# SolarPwrOptions.net
KiCad netlist of a schematic drawn in EAGLE
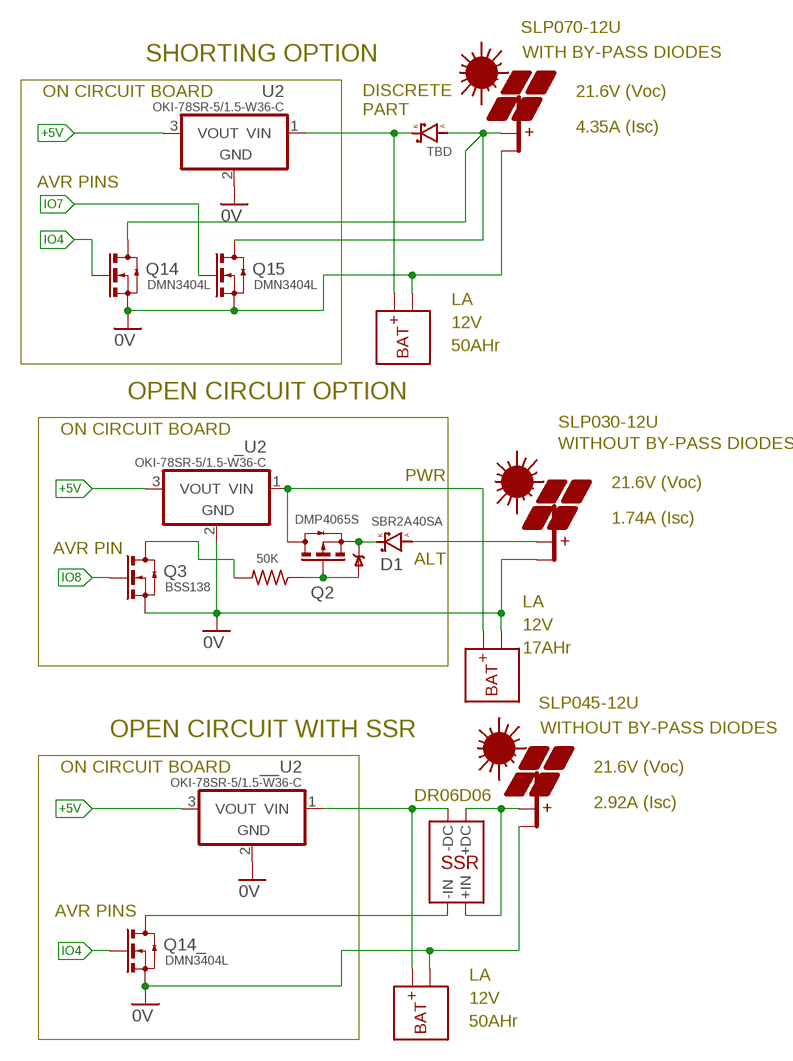
[diagram p0: schematic, sheet 1]

(export (version "E")
  (design (tool "Eeschema 10.0.6"))
  (components
    (comp (ref "D1")
      (value "SBR2A40SA")
      (footprint "eagle-import:SMB")
      (libsource (lib "eagle-import") (part "DSMB"))
    )
    (comp (ref "D3")
      (value "TVSSMC")
      (footprint "eagle-import:SMC")
      (libsource (lib "eagle-import") (part "TVSSMC"))
    )
    (comp (ref "PV1")
      (value "PV")
      (footprint "eagle-import:NA-30")
      (libsource (lib "eagle-import") (part "PV"))
    )
    (comp (ref "PV2")
      (value "PV")
      (footprint "eagle-import:NA-30")
      (libsource (lib "eagle-import") (part "PV"))
    )
    (comp (ref "PV3")
      (value "PV")
      (footprint "eagle-import:NA-30")
      (libsource (lib "eagle-import") (part "PV"))
    )
    (comp (ref "Q2")
      (value "DMP4065S")
      (footprint "eagle-import:DPAK")
      (libsource (lib "eagle-import") (part "Q-PCH_N-CH?DPAK"))
    )
    (comp (ref "Q3")
      (value "BSS138")
      (footprint "eagle-import:DPAK")
      (libsource (lib "eagle-import") (part "N-CH?DPAK"))
    )
    (comp (ref "Q14")
      (value "DMN3404L")
      (footprint "eagle-import:DPAK")
      (libsource (lib "eagle-import") (part "N-CH?DPAK"))
    )
    (comp (ref "Q14_")
      (value "DMN3404L")
      (footprint "eagle-import:DPAK")
      (libsource (lib "eagle-import") (part "N-CH?DPAK"))
    )
    (comp (ref "Q15")
      (value "DMN3404L")
      (footprint "eagle-import:DPAK")
      (libsource (lib "eagle-import") (part "N-CH?DPAK"))
    )
    (comp (ref "R2")
      (value "50K")
      (footprint "eagle-import:C0805(2012)")
      (libsource (lib "eagle-import") (part "R0805"))
    )
    (comp (ref "U$1")
      (value "BAT")
      (footprint "eagle-import:NA-30")
      (libsource (lib "eagle-import") (part "BAT"))
    )
    (comp (ref "U$2")
      (value "BAT")
      (footprint "eagle-import:NA-30")
      (libsource (lib "eagle-import") (part "BAT"))
    )
    (comp (ref "U$3")
      (value "SSR_DC")
      (footprint "eagle-import:NA-30")
      (libsource (lib "eagle-import") (part "SSR_DC"))
    )
    (comp (ref "U$10")
      (value "BAT")
      (footprint "eagle-import:NA-30")
      (libsource (lib "eagle-import") (part "BAT"))
    )
    (comp (ref "U2")
      (value "OKI-78SR-5/1.5-W36-C")
      (footprint "eagle-import:OKI-78SR-H")
      (libsource (lib "eagle-import") (part "OKI-78SR-H"))
    )
    (comp (ref "_D1")
      (value "TBD")
      (footprint "eagle-import:SMB")
      (libsource (lib "eagle-import") (part "DSMB"))
    )
    (comp (ref "_U2")
      (value "OKI-78SR-5/1.5-W36-C")
      (footprint "eagle-import:OKI-78SR-H")
      (libsource (lib "eagle-import") (part "OKI-78SR-H"))
    )
    (comp (ref "__U2")
      (value "OKI-78SR-5/1.5-W36-C")
      (footprint "eagle-import:OKI-78SR-H")
      (libsource (lib "eagle-import") (part "OKI-78SR-H"))
    )
  )
  (nets
    (net (code "1") (name "+5V") (class "Default")
      (node (ref "U2") (pin "3") (pinfunction "VOUT_3") (pintype "passive"))
      (node (ref "_U2") (pin "3") (pinfunction "VOUT_3") (pintype "passive"))
      (node (ref "__U2") (pin "3") (pinfunction "VOUT_3") (pintype "passive"))
    )
    (net (code "2") (name "0V") (class "Default")
      (node (ref "PV1") (pin "2") (pinfunction "-PV_2") (pintype "bidirectional"))
      (node (ref "PV2") (pin "2") (pinfunction "-PV_2") (pintype "bidirectional"))
      (node (ref "PV3") (pin "2") (pinfunction "-PV_2") (pintype "bidirectional"))
      (node (ref "Q14") (pin "3") (pinfunction "S_3") (pintype "passive"))
      (node (ref "Q14_") (pin "3") (pinfunction "S_3") (pintype "passive"))
      (node (ref "Q15") (pin "3") (pinfunction "S_3") (pintype "passive"))
      (node (ref "Q3") (pin "3") (pinfunction "S_3") (pintype "passive"))
      (node (ref "U$1") (pin "2") (pinfunction "-BAT_2") (pintype "bidirectional"))
      (node (ref "U$10") (pin "2") (pinfunction "-BAT_2") (pintype "bidirectional"))
      (node (ref "U$2") (pin "2") (pinfunction "-BAT_2") (pintype "bidirectional"))
      (node (ref "U2") (pin "2") (pinfunction "GND_2") (pintype "passive"))
      (node (ref "_U2") (pin "2") (pinfunction "GND_2") (pintype "passive"))
      (node (ref "__U2") (pin "2") (pinfunction "GND_2") (pintype "passive"))
    )
    (net (code "3") (name "IO4") (class "Default")
      (node (ref "Q14") (pin "1") (pinfunction "G_1") (pintype "passive"))
      (node (ref "Q14_") (pin "1") (pinfunction "G_1") (pintype "passive"))
    )
    (net (code "4") (name "IO7") (class "Default")
      (node (ref "Q15") (pin "1") (pinfunction "G_1") (pintype "passive"))
    )
    (net (code "5") (name "IO8") (class "Default")
      (node (ref "Q3") (pin "1") (pinfunction "G_1") (pintype "passive"))
    )
    (net (code "6") (name "Net-(PV1-+PV)") (class "Default")
      (node (ref "PV1") (pin "1") (pinfunction "+PV_1") (pintype "bidirectional"))
      (node (ref "Q14") (pin "SINK") (pinfunction "D_SINK") (pintype "passive"))
      (node (ref "Q15") (pin "SINK") (pinfunction "D_SINK") (pintype "passive"))
      (node (ref "_D1") (pin "A") (pinfunction "A_A") (pintype "passive"))
    )
    (net (code "7") (name "Net-(PV2-+PV)") (class "Default")
      (node (ref "D1") (pin "A") (pinfunction "A_A") (pintype "passive"))
      (node (ref "PV2") (pin "1") (pinfunction "+PV_1") (pintype "bidirectional"))
    )
    (net (code "8") (name "Net-(PV3-+PV)") (class "Default")
      (node (ref "PV3") (pin "1") (pinfunction "+PV_1") (pintype "bidirectional"))
      (node (ref "U$3") (pin "1") (pinfunction "+DC_1") (pintype "bidirectional"))
      (node (ref "U$3") (pin "2") (pinfunction "+IN_2") (pintype "bidirectional"))
    )
    (net (code "9") (name "Net-(Q2-D)") (class "Default")
      (node (ref "Q2") (pin "SINK") (pinfunction "D_SINK") (pintype "passive"))
      (node (ref "U$1") (pin "1") (pinfunction "+BAT_1") (pintype "bidirectional"))
      (node (ref "_U2") (pin "1") (pinfunction "VIN_1") (pintype "passive"))
    )
    (net (code "10") (name "Net-(Q2-G)") (class "Default")
      (node (ref "D3") (pin "A") (pinfunction "A_A") (pintype "passive"))
      (node (ref "Q2") (pin "1") (pinfunction "G_1") (pintype "passive"))
      (node (ref "R2") (pin "1") (pinfunction "1_1") (pintype "passive"))
    )
    (net (code "11") (name "Net-(Q2-S)") (class "Default")
      (node (ref "D1") (pin "K") (pinfunction "K_K") (pintype "passive"))
      (node (ref "D3") (pin "C") (pinfunction "C_C") (pintype "passive"))
      (node (ref "Q2") (pin "3") (pinfunction "S_3") (pintype "passive"))
    )
    (net (code "12") (name "Net-(Q3-D)") (class "Default")
      (node (ref "Q3") (pin "SINK") (pinfunction "D_SINK") (pintype "passive"))
      (node (ref "R2") (pin "2") (pinfunction "2_2") (pintype "passive"))
    )
    (net (code "13") (name "Net-(Q14_-D)") (class "Default")
      (node (ref "Q14_") (pin "SINK") (pinfunction "D_SINK") (pintype "passive"))
      (node (ref "U$3") (pin "4") (pinfunction "-IN_4") (pintype "bidirectional"))
    )
    (net (code "14") (name "Net-(U$2-+BAT)") (class "Default")
      (node (ref "U$2") (pin "1") (pinfunction "+BAT_1") (pintype "bidirectional"))
      (node (ref "U$3") (pin "3") (pinfunction "-DC_3") (pintype "bidirectional"))
      (node (ref "__U2") (pin "1") (pinfunction "VIN_1") (pintype "passive"))
    )
    (net (code "15") (name "Net-(U$10-+BAT)") (class "Default")
      (node (ref "U$10") (pin "1") (pinfunction "+BAT_1") (pintype "bidirectional"))
      (node (ref "U2") (pin "1") (pinfunction "VIN_1") (pintype "passive"))
      (node (ref "_D1") (pin "K") (pinfunction "K_K") (pintype "passive"))
    )
  )
)
